# timetracker-1-1.net
KiCad netlist of a schematic drawn in EAGLE
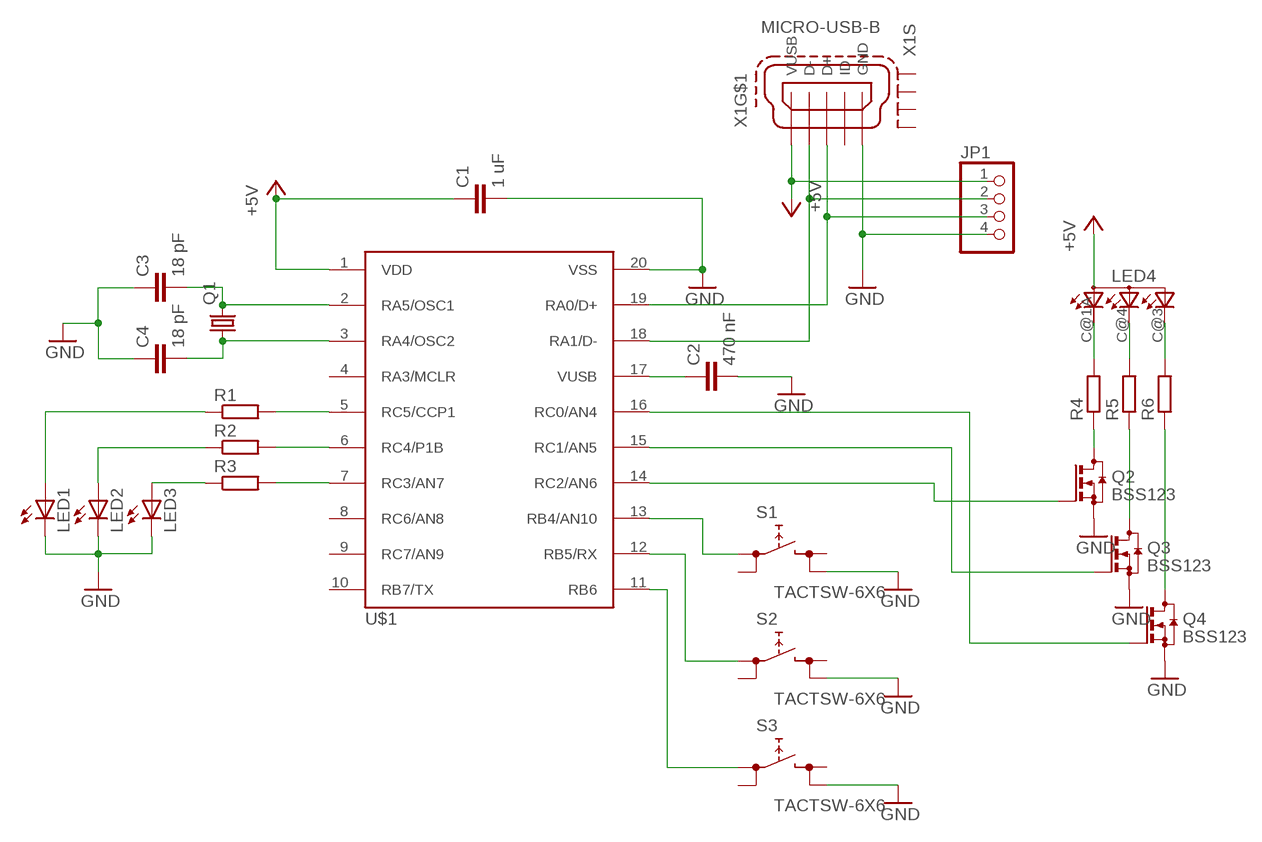
[diagram p0: schematic, sheet 1]

(export (version "E")
  (design (tool "Eeschema 10.0.6"))
  (components
    (comp (ref "C1")
      (value "1 uF")
      (footprint "eagle-import:C0805")
      (libsource (lib "eagle-import") (part "C-EUC0805"))
    )
    (comp (ref "C2")
      (value "470 nF")
      (footprint "eagle-import:C0805")
      (libsource (lib "eagle-import") (part "C-EUC0805"))
    )
    (comp (ref "C3")
      (value "18 pF")
      (footprint "eagle-import:C0805")
      (libsource (lib "eagle-import") (part "C-EUC0805"))
    )
    (comp (ref "C4")
      (value "18 pF")
      (footprint "eagle-import:C0805")
      (libsource (lib "eagle-import") (part "C-EUC0805"))
    )
    (comp (ref "JP1")
      (value "PINHD-1X4")
      (footprint "eagle-import:1X04")
      (libsource (lib "eagle-import") (part "PINHD-1X4"))
    )
    (comp (ref "LED1")
      (value "LEDSML0805")
      (footprint "eagle-import:SML0805")
      (libsource (lib "eagle-import") (part "LEDSML0805"))
    )
    (comp (ref "LED2")
      (value "LEDSML0805")
      (footprint "eagle-import:SML0805")
      (libsource (lib "eagle-import") (part "LEDSML0805"))
    )
    (comp (ref "LED3")
      (value "LEDSML0805")
      (footprint "eagle-import:SML0805")
      (libsource (lib "eagle-import") (part "LEDSML0805"))
    )
    (comp (ref "LED4")
      (value "RGBLED-3P-LCC-4")
      (footprint "eagle-import:P-LCC-4")
      (libsource (lib "eagle-import") (part "RGBLED-3P-LCC-4"))
    )
    (comp (ref "Q1")
      (value "CRYSTALHC49UP")
      (footprint "eagle-import:HC49UP")
      (libsource (lib "eagle-import") (part "CRYSTALHC49UP"))
    )
    (comp (ref "Q2")
      (value "BSS123")
      (footprint "eagle-import:SOT23")
      (libsource (lib "eagle-import") (part "BSS123"))
    )
    (comp (ref "Q3")
      (value "BSS123")
      (footprint "eagle-import:SOT23")
      (libsource (lib "eagle-import") (part "BSS123"))
    )
    (comp (ref "Q4")
      (value "BSS123")
      (footprint "eagle-import:SOT23")
      (libsource (lib "eagle-import") (part "BSS123"))
    )
    (comp (ref "R1")
      (value "R-EU_R0805")
      (footprint "eagle-import:R0805")
      (libsource (lib "eagle-import") (part "R-EU_R0805"))
    )
    (comp (ref "R2")
      (value "R-EU_R0805")
      (footprint "eagle-import:R0805")
      (libsource (lib "eagle-import") (part "R-EU_R0805"))
    )
    (comp (ref "R3")
      (value "R-EU_R0805")
      (footprint "eagle-import:R0805")
      (libsource (lib "eagle-import") (part "R-EU_R0805"))
    )
    (comp (ref "R4")
      (value "R-EU_R0805")
      (footprint "eagle-import:R0805")
      (libsource (lib "eagle-import") (part "R-EU_R0805"))
    )
    (comp (ref "R5")
      (value "R-EU_R0805")
      (footprint "eagle-import:R0805")
      (libsource (lib "eagle-import") (part "R-EU_R0805"))
    )
    (comp (ref "R6")
      (value "R-EU_R0805")
      (footprint "eagle-import:R0805")
      (libsource (lib "eagle-import") (part "R-EU_R0805"))
    )
    (comp (ref "S1")
      (value "TACTSW-6X6")
      (footprint "eagle-import:TACTSW-6X6")
      (libsource (lib "eagle-import") (part "TACTSW-6X6"))
    )
    (comp (ref "S2")
      (value "TACTSW-6X6")
      (footprint "eagle-import:TACTSW-6X6")
      (libsource (lib "eagle-import") (part "TACTSW-6X6"))
    )
    (comp (ref "S3")
      (value "TACTSW-6X6")
      (footprint "eagle-import:TACTSW-6X6")
      (libsource (lib "eagle-import") (part "TACTSW-6X6"))
    )
    (comp (ref "U$1")
      (value "PIC18F14K50")
      (footprint "eagle-import:DIL20")
      (libsource (lib "eagle-import") (part "PIC18F14K50"))
    )
    (comp (ref "X1")
      (value "MICRO-USB-B")
      (footprint "eagle-import:MICRO-B-PAC")
      (libsource (lib "eagle-import") (part "MICRO-USB-B"))
    )
  )
  (nets
    (net (code "1") (name "+5V") (class "Default")
      (node (ref "C1") (pin "1") (pinfunction "1_1") (pintype "passive"))
      (node (ref "JP1") (pin "1") (pinfunction "1_1") (pintype "passive"))
      (node (ref "LED4") (pin "A") (pinfunction "A2_A") (pintype "passive"))
      (node (ref "U$1") (pin "1") (pinfunction "VDD_1") (pintype "bidirectional"))
      (node (ref "X1") (pin "1") (pinfunction "VUSB_1") (pintype "passive"))
    )
    (net (code "2") (name "GND") (class "Default")
      (node (ref "C1") (pin "2") (pinfunction "2_2") (pintype "passive"))
      (node (ref "C2") (pin "2") (pinfunction "2_2") (pintype "passive"))
      (node (ref "C3") (pin "1") (pinfunction "1_1") (pintype "passive"))
      (node (ref "C4") (pin "1") (pinfunction "1_1") (pintype "passive"))
      (node (ref "JP1") (pin "4") (pinfunction "4_4") (pintype "passive"))
      (node (ref "LED1") (pin "C") (pinfunction "C_C") (pintype "passive"))
      (node (ref "LED2") (pin "C") (pinfunction "C_C") (pintype "passive"))
      (node (ref "LED3") (pin "C") (pinfunction "C_C") (pintype "passive"))
      (node (ref "Q2") (pin "2") (pinfunction "S_2") (pintype "passive"))
      (node (ref "Q3") (pin "2") (pinfunction "S_2") (pintype "passive"))
      (node (ref "Q4") (pin "2") (pinfunction "S_2") (pintype "passive"))
      (node (ref "S1") (pin "4") (pinfunction "2.2_4") (pintype "passive"))
      (node (ref "S2") (pin "4") (pinfunction "2.2_4") (pintype "passive"))
      (node (ref "S3") (pin "4") (pinfunction "2.2_4") (pintype "passive"))
      (node (ref "U$1") (pin "20") (pinfunction "VSS_20") (pintype "bidirectional"))
      (node (ref "X1") (pin "5") (pinfunction "GND_5") (pintype "passive"))
    )
    (net (code "3") (name "Net-(LED1-PadA)") (class "Default")
      (node (ref "LED1") (pin "A") (pinfunction "A_A") (pintype "passive"))
      (node (ref "R1") (pin "1") (pinfunction "1_1") (pintype "passive"))
    )
    (net (code "4") (name "Net-(LED2-PadA)") (class "Default")
      (node (ref "LED2") (pin "A") (pinfunction "A_A") (pintype "passive"))
      (node (ref "R2") (pin "1") (pinfunction "1_1") (pintype "passive"))
    )
    (net (code "5") (name "Net-(LED3-PadA)") (class "Default")
      (node (ref "LED3") (pin "A") (pinfunction "A_A") (pintype "passive"))
      (node (ref "R3") (pin "1") (pinfunction "1_1") (pintype "passive"))
    )
    (net (code "6") (name "Net-(LED4-CBLUE)") (class "Default")
      (node (ref "LED4") (pin "C@3") (pinfunction "CBLUE_C@3") (pintype "passive"))
      (node (ref "R6") (pin "2") (pinfunction "2_2") (pintype "passive"))
    )
    (net (code "7") (name "Net-(LED4-CGREEN)") (class "Default")
      (node (ref "LED4") (pin "C@4") (pinfunction "CGREEN_C@4") (pintype "passive"))
      (node (ref "R5") (pin "2") (pinfunction "2_2") (pintype "passive"))
    )
    (net (code "8") (name "Net-(LED4-CRED)") (class "Default")
      (node (ref "LED4") (pin "C@1") (pinfunction "CRED_C@1") (pintype "passive"))
      (node (ref "R4") (pin "2") (pinfunction "2_2") (pintype "passive"))
    )
    (net (code "9") (name "Net-(Q2-D)") (class "Default")
      (node (ref "Q2") (pin "3") (pinfunction "D_3") (pintype "passive"))
      (node (ref "R4") (pin "1") (pinfunction "1_1") (pintype "passive"))
    )
    (net (code "10") (name "Net-(Q2-G)") (class "Default")
      (node (ref "Q2") (pin "1") (pinfunction "G_1") (pintype "passive"))
      (node (ref "U$1") (pin "14") (pinfunction "RC2/AN6_14") (pintype "bidirectional"))
    )
    (net (code "11") (name "Net-(Q3-D)") (class "Default")
      (node (ref "Q3") (pin "3") (pinfunction "D_3") (pintype "passive"))
      (node (ref "R5") (pin "1") (pinfunction "1_1") (pintype "passive"))
    )
    (net (code "12") (name "Net-(Q3-G)") (class "Default")
      (node (ref "Q3") (pin "1") (pinfunction "G_1") (pintype "passive"))
      (node (ref "U$1") (pin "15") (pinfunction "RC1/AN5_15") (pintype "bidirectional"))
    )
    (net (code "13") (name "Net-(Q4-D)") (class "Default")
      (node (ref "Q4") (pin "3") (pinfunction "D_3") (pintype "passive"))
      (node (ref "R6") (pin "1") (pinfunction "1_1") (pintype "passive"))
    )
    (net (code "14") (name "Net-(Q4-G)") (class "Default")
      (node (ref "Q4") (pin "1") (pinfunction "G_1") (pintype "passive"))
      (node (ref "U$1") (pin "16") (pinfunction "RC0/AN4_16") (pintype "bidirectional"))
    )
    (net (code "15") (name "Net-(S1-1.1)") (class "Default")
      (node (ref "S1") (pin "1") (pinfunction "1.1_1") (pintype "passive"))
      (node (ref "U$1") (pin "13") (pinfunction "RB4/AN10_13") (pintype "bidirectional"))
    )
    (net (code "16") (name "Net-(S2-1.1)") (class "Default")
      (node (ref "S2") (pin "1") (pinfunction "1.1_1") (pintype "passive"))
      (node (ref "U$1") (pin "12") (pinfunction "RB5/RX_12") (pintype "bidirectional"))
    )
    (net (code "17") (name "Net-(S3-1.1)") (class "Default")
      (node (ref "S3") (pin "1") (pinfunction "1.1_1") (pintype "passive"))
      (node (ref "U$1") (pin "11") (pinfunction "RB6_11") (pintype "bidirectional"))
    )
    (net (code "18") (name "Net-(U$1-RA0{slash}D+)") (class "Default")
      (node (ref "JP1") (pin "3") (pinfunction "3_3") (pintype "passive"))
      (node (ref "U$1") (pin "19") (pinfunction "RA0/D+_19") (pintype "bidirectional"))
      (node (ref "X1") (pin "3") (pinfunction "D+_3") (pintype "passive"))
    )
    (net (code "19") (name "Net-(U$1-RA1{slash}D-)") (class "Default")
      (node (ref "JP1") (pin "2") (pinfunction "2_2") (pintype "passive"))
      (node (ref "U$1") (pin "18") (pinfunction "RA1/D-_18") (pintype "bidirectional"))
      (node (ref "X1") (pin "2") (pinfunction "D-_2") (pintype "passive"))
    )
    (net (code "20") (name "Net-(U$1-RA4{slash}OSC2)") (class "Default")
      (node (ref "C4") (pin "2") (pinfunction "2_2") (pintype "passive"))
      (node (ref "Q1") (pin "1") (pinfunction "1_1") (pintype "passive"))
      (node (ref "U$1") (pin "3") (pinfunction "RA4/OSC2_3") (pintype "bidirectional"))
    )
    (net (code "21") (name "Net-(U$1-RA5{slash}OSC1)") (class "Default")
      (node (ref "C3") (pin "2") (pinfunction "2_2") (pintype "passive"))
      (node (ref "Q1") (pin "2") (pinfunction "2_2") (pintype "passive"))
      (node (ref "U$1") (pin "2") (pinfunction "RA5/OSC1_2") (pintype "bidirectional"))
    )
    (net (code "22") (name "Net-(U$1-RC3{slash}AN7)") (class "Default")
      (node (ref "R3") (pin "2") (pinfunction "2_2") (pintype "passive"))
      (node (ref "U$1") (pin "7") (pinfunction "RC3/AN7_7") (pintype "bidirectional"))
    )
    (net (code "23") (name "Net-(U$1-RC4{slash}P1B)") (class "Default")
      (node (ref "R2") (pin "2") (pinfunction "2_2") (pintype "passive"))
      (node (ref "U$1") (pin "6") (pinfunction "RC4/P1B_6") (pintype "bidirectional"))
    )
    (net (code "24") (name "Net-(U$1-RC5{slash}CCP1)") (class "Default")
      (node (ref "R1") (pin "2") (pinfunction "2_2") (pintype "passive"))
      (node (ref "U$1") (pin "5") (pinfunction "RC5/CCP1_5") (pintype "bidirectional"))
    )
    (net (code "25") (name "Net-(U$1-VUSB)") (class "Default")
      (node (ref "C2") (pin "1") (pinfunction "1_1") (pintype "passive"))
      (node (ref "U$1") (pin "17") (pinfunction "VUSB_17") (pintype "bidirectional"))
    )
    (net (code "26") (name "unconnected-(S1-1.2-Pad2)") (class "Default")
      (node (ref "S1") (pin "2") (pinfunction "1.2_2") (pintype "passive"))
    )
    (net (code "27") (name "unconnected-(S1-2.1-Pad3)") (class "Default")
      (node (ref "S1") (pin "3") (pinfunction "2.1_3") (pintype "passive"))
    )
    (net (code "28") (name "unconnected-(S2-1.2-Pad2)") (class "Default")
      (node (ref "S2") (pin "2") (pinfunction "1.2_2") (pintype "passive"))
    )
    (net (code "29") (name "unconnected-(S2-2.1-Pad3)") (class "Default")
      (node (ref "S2") (pin "3") (pinfunction "2.1_3") (pintype "passive"))
    )
    (net (code "30") (name "unconnected-(S3-1.2-Pad2)") (class "Default")
      (node (ref "S3") (pin "2") (pinfunction "1.2_2") (pintype "passive"))
    )
    (net (code "31") (name "unconnected-(S3-2.1-Pad3)") (class "Default")
      (node (ref "S3") (pin "3") (pinfunction "2.1_3") (pintype "passive"))
    )
    (net (code "32") (name "unconnected-(U$1-RA3{slash}MCLR-Pad4)") (class "Default")
      (node (ref "U$1") (pin "4") (pinfunction "RA3/MCLR_4") (pintype "bidirectional"))
    )
    (net (code "33") (name "unconnected-(U$1-RB7{slash}TX-Pad10)") (class "Default")
      (node (ref "U$1") (pin "10") (pinfunction "RB7/TX_10") (pintype "bidirectional"))
    )
    (net (code "34") (name "unconnected-(U$1-RC6{slash}AN8-Pad8)") (class "Default")
      (node (ref "U$1") (pin "8") (pinfunction "RC6/AN8_8") (pintype "bidirectional"))
    )
    (net (code "35") (name "unconnected-(U$1-RC7{slash}AN9-Pad9)") (class "Default")
      (node (ref "U$1") (pin "9") (pinfunction "RC7/AN9_9") (pintype "bidirectional"))
    )
    (net (code "36") (name "unconnected-(X1A-ID-Pad4)") (class "Default")
      (node (ref "X1") (pin "4") (pinfunction "ID_4") (pintype "passive"))
    )
    (net (code "37") (name "unconnected-(X1B-S1-PadM1)") (class "Default")
      (node (ref "X1") (pin "M1") (pinfunction "S1_M1") (pintype "passive"))
    )
    (net (code "38") (name "unconnected-(X1B-S2-PadM2)") (class "Default")
      (node (ref "X1") (pin "M2") (pinfunction "S2_M2") (pintype "passive"))
    )
    (net (code "39") (name "unconnected-(X1B-S3-PadM3)") (class "Default")
      (node (ref "X1") (pin "M3") (pinfunction "S3_M3") (pintype "passive"))
    )
    (net (code "40") (name "unconnected-(X1B-S4-PadM4)") (class "Default")
      (node (ref "X1") (pin "M4") (pinfunction "S4_M4") (pintype "passive"))
    )
  )
)
